# V3.net
KiCad netlist of a schematic drawn in EAGLE
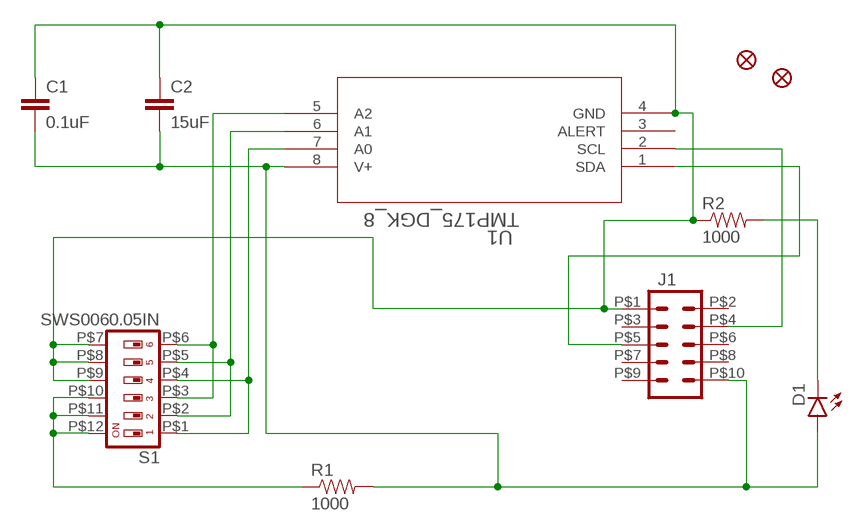
[diagram p0: schematic, sheet 1]

(export (version "E")
  (design (tool "Eeschema 10.0.6"))
  (components
    (comp (ref "C1")
      (value "0.1uF")
      (footprint "eagle-import:0805")
      (libsource (lib "eagle-import") (part "22UF-6.3V-20%(0805)"))
    )
    (comp (ref "C2")
      (value "15uF")
      (footprint "eagle-import:0805")
      (libsource (lib "eagle-import") (part "CAP0805"))
    )
    (comp (ref "D1")
      (value "LED-BLUE1206")
      (footprint "eagle-import:LED-1206")
      (libsource (lib "eagle-import") (part "LED-BLUE1206"))
    )
    (comp (ref "FID1")
      (value "FIDUCIAL1X2")
      (footprint "eagle-import:FIDUCIAL-1X2")
      (libsource (lib "eagle-import") (part "FIDUCIAL1X2"))
    )
    (comp (ref "FID3")
      (value "FIDUCIAL1X2")
      (footprint "eagle-import:FIDUCIAL-1X2")
      (libsource (lib "eagle-import") (part "FIDUCIAL1X2"))
    )
    (comp (ref "J1")
      (value "M05X22X5-UNSHROUDED_SMD")
      (footprint "eagle-import:2X5-UNSHROUDED_SMD")
      (libsource (lib "eagle-import") (part "M05X22X5-UNSHROUDED_SMD"))
    )
    (comp (ref "R1")
      (value "1000")
      (footprint "eagle-import:0805")
      (libsource (lib "eagle-import") (part "RESISTOR0805-RES"))
    )
    (comp (ref "R2")
      (value "1000")
      (footprint "eagle-import:0805")
      (libsource (lib "eagle-import") (part "RESISTOR0805-RES"))
    )
    (comp (ref "S1")
      (value "SWS0060.05IN")
      (footprint "eagle-import:SMS-006")
      (libsource (lib "eagle-import") (part "SWS0060.05IN"))
    )
    (comp (ref "U1")
      (value "TMP175_DGK_8")
      (footprint "eagle-import:DGK8")
      (fields
        (field (name "GENERIC_PART_NUMBER") "TMP175")
        (field (name "MANUFACTURER") "Texas Instruments")
        (field (name "MANUFACTURER_PART_NUMBER") "tmp175_dgk_8")
      )
      (libsource (lib "eagle-import") (part "TMP175_DGK_8"))
    )
  )
  (nets
    (net (code "1") (name "Net-(D1-PadC)") (class "Default")
      (node (ref "D1") (pin "C") (pinfunction "C_C") (pintype "passive"))
      (node (ref "R2") (pin "2") (pinfunction "2_2") (pintype "passive"))
    )
    (net (code "2") (name "Net-(J1-1)") (class "Default")
      (node (ref "C1") (pin "1") (pinfunction "1_1") (pintype "passive"))
      (node (ref "C2") (pin "1") (pinfunction "1_1") (pintype "passive"))
      (node (ref "J1") (pin "P$1") (pinfunction "1_P$1") (pintype "passive"))
      (node (ref "R2") (pin "1") (pinfunction "1_1") (pintype "passive"))
      (node (ref "S1") (pin "P$7") (pinfunction "7_P$7") (pintype "passive"))
      (node (ref "S1") (pin "P$8") (pinfunction "8_P$8") (pintype "passive"))
      (node (ref "S1") (pin "P$9") (pinfunction "9_P$9") (pintype "passive"))
      (node (ref "U1") (pin "4") (pinfunction "GND_4") (pintype "power_in"))
    )
    (net (code "3") (name "Net-(J1-4)") (class "Default")
      (node (ref "J1") (pin "P$4") (pinfunction "4_P$4") (pintype "passive"))
      (node (ref "U1") (pin "2") (pinfunction "SCL_2") (pintype "bidirectional"))
    )
    (net (code "4") (name "Net-(J1-5)") (class "Default")
      (node (ref "J1") (pin "P$5") (pinfunction "5_P$5") (pintype "passive"))
      (node (ref "U1") (pin "1") (pinfunction "SDA_1") (pintype "bidirectional"))
    )
    (net (code "5") (name "Net-(J1-10)") (class "Default")
      (node (ref "C1") (pin "2") (pinfunction "2_2") (pintype "passive"))
      (node (ref "C2") (pin "2") (pinfunction "2_2") (pintype "passive"))
      (node (ref "D1") (pin "A") (pinfunction "A_A") (pintype "passive"))
      (node (ref "J1") (pin "P$10") (pinfunction "10_P$10") (pintype "passive"))
      (node (ref "R1") (pin "2") (pinfunction "2_2") (pintype "passive"))
      (node (ref "U1") (pin "8") (pinfunction "V+_8") (pintype "power_in"))
    )
    (net (code "6") (name "Net-(S1-1)") (class "Default")
      (node (ref "S1") (pin "P$1") (pinfunction "1_P$1") (pintype "passive"))
      (node (ref "S1") (pin "P$4") (pinfunction "4_P$4") (pintype "passive"))
      (node (ref "U1") (pin "7") (pinfunction "A0_7") (pintype "bidirectional"))
    )
    (net (code "7") (name "Net-(S1-2)") (class "Default")
      (node (ref "S1") (pin "P$2") (pinfunction "2_P$2") (pintype "passive"))
      (node (ref "S1") (pin "P$5") (pinfunction "5_P$5") (pintype "passive"))
      (node (ref "U1") (pin "6") (pinfunction "A1_6") (pintype "bidirectional"))
    )
    (net (code "8") (name "Net-(S1-3)") (class "Default")
      (node (ref "S1") (pin "P$3") (pinfunction "3_P$3") (pintype "passive"))
      (node (ref "S1") (pin "P$6") (pinfunction "6_P$6") (pintype "passive"))
      (node (ref "U1") (pin "5") (pinfunction "A2_5") (pintype "bidirectional"))
    )
    (net (code "9") (name "Net-(S1-10)") (class "Default")
      (node (ref "R1") (pin "1") (pinfunction "1_1") (pintype "passive"))
      (node (ref "S1") (pin "P$10") (pinfunction "10_P$10") (pintype "passive"))
      (node (ref "S1") (pin "P$11") (pinfunction "11_P$11") (pintype "passive"))
      (node (ref "S1") (pin "P$12") (pinfunction "12_P$12") (pintype "passive"))
    )
    (net (code "10") (name "unconnected-(J1-2-PadP$2)") (class "Default")
      (node (ref "J1") (pin "P$2") (pinfunction "2_P$2") (pintype "passive"))
    )
    (net (code "11") (name "unconnected-(J1-3-PadP$3)") (class "Default")
      (node (ref "J1") (pin "P$3") (pinfunction "3_P$3") (pintype "passive"))
    )
    (net (code "12") (name "unconnected-(J1-6-PadP$6)") (class "Default")
      (node (ref "J1") (pin "P$6") (pinfunction "6_P$6") (pintype "passive"))
    )
    (net (code "13") (name "unconnected-(J1-7-PadP$7)") (class "Default")
      (node (ref "J1") (pin "P$7") (pinfunction "7_P$7") (pintype "passive"))
    )
    (net (code "14") (name "unconnected-(J1-8-PadP$8)") (class "Default")
      (node (ref "J1") (pin "P$8") (pinfunction "8_P$8") (pintype "passive"))
    )
    (net (code "15") (name "unconnected-(J1-9-PadP$9)") (class "Default")
      (node (ref "J1") (pin "P$9") (pinfunction "9_P$9") (pintype "passive"))
    )
    (net (code "16") (name "unconnected-(U1-ALERT-Pad3)") (class "Default")
      (node (ref "U1") (pin "3") (pinfunction "ALERT_3") (pintype "bidirectional"))
    )
  )
)
